# amp01.net
KiCad netlist of a schematic drawn in EAGLE
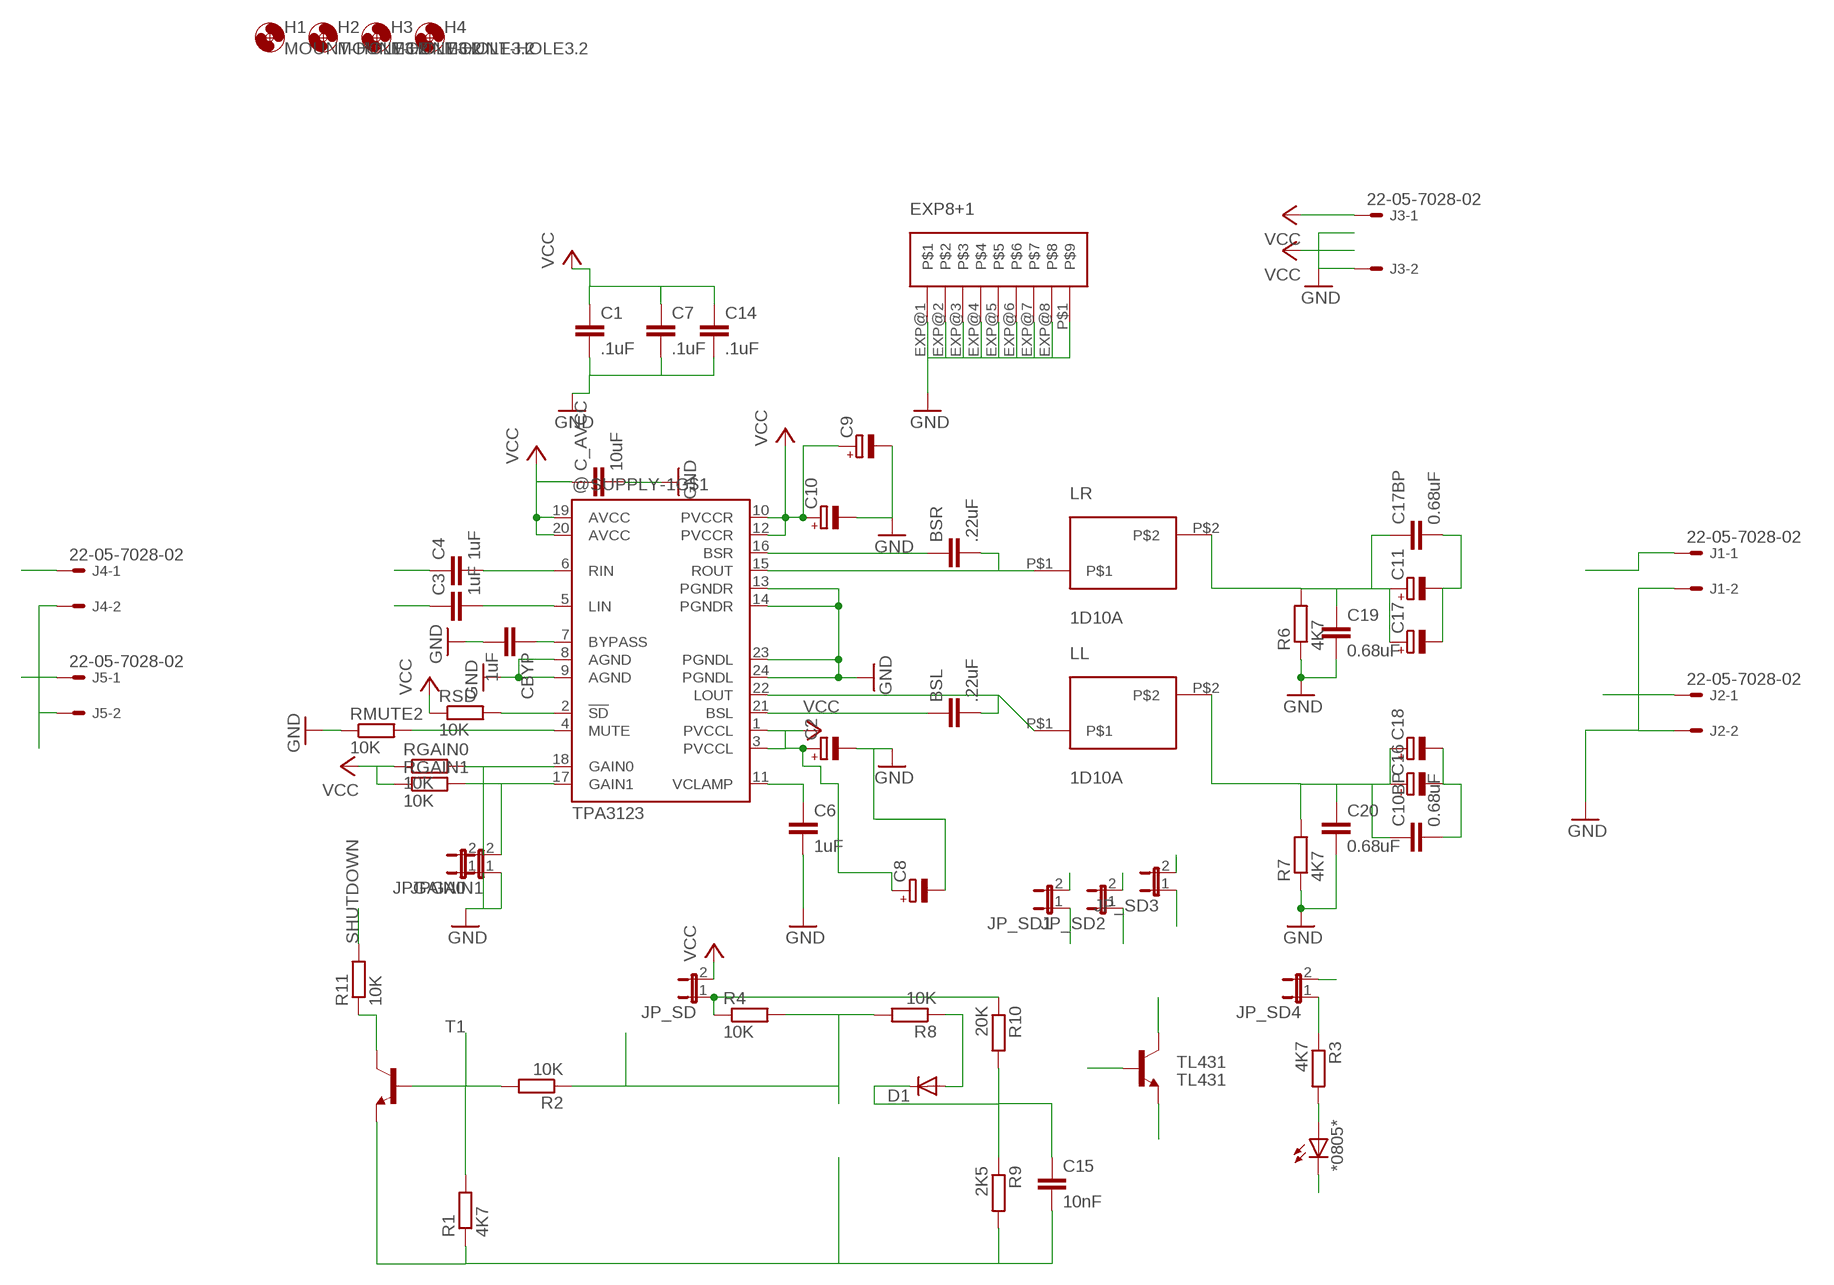
[diagram p0: schematic, sheet 1]

(export (version "E")
  (design (tool "Eeschema 10.0.6"))
  (components
    (comp (ref "*0805*")
      (value "LEDCHIP-LED0805")
      (footprint "eagle-import:CHIP-LED0805")
      (libsource (lib "eagle-import") (part "LEDCHIP-LED0805"))
    )
    (comp (ref "@SUPPLY-1")
      (value "TPA3123")
      (footprint "eagle-import:PWP-TSSOP24")
      (libsource (lib "eagle-import") (part "TPA3123"))
    )
    (comp (ref "BSL")
      (value ".22uF")
      (footprint "eagle-import:C0805")
      (libsource (lib "eagle-import") (part "C-EUC0805"))
    )
    (comp (ref "BSR")
      (value ".22uF")
      (footprint "eagle-import:C0805")
      (libsource (lib "eagle-import") (part "C-EUC0805"))
    )
    (comp (ref "C1")
      (value ".1uF")
      (footprint "eagle-import:C0805")
      (libsource (lib "eagle-import") (part "C-EUC0805"))
    )
    (comp (ref "C2")
      (value "CPOL-EUF")
      (footprint "eagle-import:PANASONIC_F")
      (libsource (lib "eagle-import") (part "CPOL-EUF"))
    )
    (comp (ref "C3")
      (value "1uF")
      (footprint "eagle-import:C050-050X075")
      (libsource (lib "eagle-import") (part "C-EU050-050X075"))
    )
    (comp (ref "C4")
      (value "1uF")
      (footprint "eagle-import:C050-050X075")
      (libsource (lib "eagle-import") (part "C-EU050-050X075"))
    )
    (comp (ref "C6")
      (value "1uF")
      (footprint "eagle-import:C0805")
      (libsource (lib "eagle-import") (part "C-EUC0805"))
    )
    (comp (ref "C7")
      (value ".1uF")
      (footprint "eagle-import:C0805")
      (libsource (lib "eagle-import") (part "C-EUC0805"))
    )
    (comp (ref "C8")
      (value "CPOL-EUF")
      (footprint "eagle-import:PANASONIC_F")
      (libsource (lib "eagle-import") (part "CPOL-EUF"))
    )
    (comp (ref "C9")
      (value "CPOL-EUF")
      (footprint "eagle-import:PANASONIC_F")
      (libsource (lib "eagle-import") (part "CPOL-EUF"))
    )
    (comp (ref "C10")
      (value "CPOL-EUF")
      (footprint "eagle-import:PANASONIC_F")
      (libsource (lib "eagle-import") (part "CPOL-EUF"))
    )
    (comp (ref "C10BP")
      (value "0.68uF")
      (footprint "eagle-import:C050-055X075")
      (libsource (lib "eagle-import") (part "C-EU050-055X075"))
    )
    (comp (ref "C11")
      (value "CPOL-EUF")
      (footprint "eagle-import:PANASONIC_F")
      (libsource (lib "eagle-import") (part "CPOL-EUF"))
    )
    (comp (ref "C14")
      (value ".1uF")
      (footprint "eagle-import:C0805")
      (libsource (lib "eagle-import") (part "C-EUC0805"))
    )
    (comp (ref "C15")
      (value "10nF")
      (footprint "eagle-import:C0805")
      (libsource (lib "eagle-import") (part "C-EUC0805"))
    )
    (comp (ref "C16")
      (value "CPOL-EUF")
      (footprint "eagle-import:PANASONIC_F")
      (libsource (lib "eagle-import") (part "CPOL-EUF"))
    )
    (comp (ref "C17")
      (value "CPOL-EUF")
      (footprint "eagle-import:PANASONIC_F")
      (libsource (lib "eagle-import") (part "CPOL-EUF"))
    )
    (comp (ref "C17BP")
      (value "0.68uF")
      (footprint "eagle-import:C050-055X075")
      (libsource (lib "eagle-import") (part "C-EU050-055X075"))
    )
    (comp (ref "C18")
      (value "CPOL-EUF")
      (footprint "eagle-import:PANASONIC_F")
      (libsource (lib "eagle-import") (part "CPOL-EUF"))
    )
    (comp (ref "C19")
      (value "0.68uF")
      (footprint "eagle-import:C050-055X075")
      (libsource (lib "eagle-import") (part "C-EU050-055X075"))
    )
    (comp (ref "C20")
      (value "0.68uF")
      (footprint "eagle-import:C050-055X075")
      (libsource (lib "eagle-import") (part "C-EU050-055X075"))
    )
    (comp (ref "CBYP")
      (value "1uF")
      (footprint "eagle-import:C0805")
      (libsource (lib "eagle-import") (part "C-EUC0805"))
    )
    (comp (ref "C_AVCC")
      (value "10uF")
      (footprint "eagle-import:C1210")
      (libsource (lib "eagle-import") (part "C-EUC1210"))
    )
    (comp (ref "D1")
      (value "DIODE-MICROMELF-W")
      (footprint "eagle-import:MICROMELF-W")
      (libsource (lib "eagle-import") (part "DIODE-MICROMELF-W"))
    )
    (comp (ref "H1")
      (value "MOUNT-HOLE3.2")
      (footprint "eagle-import:3,2")
      (libsource (lib "eagle-import") (part "MOUNT-HOLE3.2"))
    )
    (comp (ref "H2")
      (value "MOUNT-HOLE3.2")
      (footprint "eagle-import:3,2")
      (libsource (lib "eagle-import") (part "MOUNT-HOLE3.2"))
    )
    (comp (ref "H3")
      (value "MOUNT-HOLE3.2")
      (footprint "eagle-import:3,2")
      (libsource (lib "eagle-import") (part "MOUNT-HOLE3.2"))
    )
    (comp (ref "H4")
      (value "MOUNT-HOLE3.2")
      (footprint "eagle-import:3,2")
      (libsource (lib "eagle-import") (part "MOUNT-HOLE3.2"))
    )
    (comp (ref "J1")
      (value "22-05-7028-02")
      (footprint "eagle-import:7395-02")
      (libsource (lib "eagle-import") (part "22-?-0205-7028"))
    )
    (comp (ref "J2")
      (value "22-05-7028-02")
      (footprint "eagle-import:7395-02")
      (libsource (lib "eagle-import") (part "22-?-0205-7028"))
    )
    (comp (ref "J3")
      (value "22-05-7028-02")
      (footprint "eagle-import:7395-02")
      (fields (field (name "OC_FARNELL") "9731601") (field (name "OC_NEWARK") "unknown"))
      (libsource (lib "eagle-import") (part "22-?-0205-7028"))
    )
    (comp (ref "J4")
      (value "22-05-7028-02")
      (footprint "eagle-import:7395-02")
      (fields (field (name "OC_FARNELL") "9731601") (field (name "OC_NEWARK") "unknown"))
      (libsource (lib "eagle-import") (part "22-?-0205-7028"))
    )
    (comp (ref "J5")
      (value "22-05-7028-02")
      (footprint "eagle-import:7395-02")
      (fields (field (name "OC_FARNELL") "9731601") (field (name "OC_NEWARK") "unknown"))
      (libsource (lib "eagle-import") (part "22-?-0205-7028"))
    )
    (comp (ref "JPGAIN0")
      (value "JUMPER-2SMD-NC")
      (footprint "eagle-import:SJ_2S")
      (libsource (lib "eagle-import") (part "JUMPER-2SMD-NC"))
    )
    (comp (ref "JPGAIN1")
      (value "JUMPER-2SMD-NC")
      (footprint "eagle-import:SJ_2S")
      (libsource (lib "eagle-import") (part "JUMPER-2SMD-NC"))
    )
    (comp (ref "JP_SD")
      (value "JUMPER-2SMD-NC")
      (footprint "eagle-import:SJ_2S")
      (libsource (lib "eagle-import") (part "JUMPER-2SMD-NC"))
    )
    (comp (ref "JP_SD1")
      (value "JUMPER-2SMD-NC")
      (footprint "eagle-import:SJ_2S")
      (libsource (lib "eagle-import") (part "JUMPER-2SMD-NC"))
    )
    (comp (ref "JP_SD2")
      (value "JUMPER-2SMD-NC")
      (footprint "eagle-import:SJ_2S")
      (libsource (lib "eagle-import") (part "JUMPER-2SMD-NC"))
    )
    (comp (ref "JP_SD3")
      (value "JUMPER-2SMD-NC")
      (footprint "eagle-import:SJ_2S")
      (libsource (lib "eagle-import") (part "JUMPER-2SMD-NC"))
    )
    (comp (ref "JP_SD4")
      (value "JUMPER-2SMD-NC")
      (footprint "eagle-import:SJ_2S")
      (libsource (lib "eagle-import") (part "JUMPER-2SMD-NC"))
    )
    (comp (ref "LL")
      (value "1D10A")
      (footprint "eagle-import:1D10APAC")
      (libsource (lib "eagle-import") (part "1D10A"))
    )
    (comp (ref "LR")
      (value "1D10A")
      (footprint "eagle-import:1D10APAC")
      (libsource (lib "eagle-import") (part "1D10A"))
    )
    (comp (ref "R1")
      (value "4K7")
      (footprint "eagle-import:R0805")
      (libsource (lib "eagle-import") (part "R-EU_R0805"))
    )
    (comp (ref "R2")
      (value "10K")
      (footprint "eagle-import:R0805")
      (libsource (lib "eagle-import") (part "R-EU_R0805"))
    )
    (comp (ref "R3")
      (value "4K7")
      (footprint "eagle-import:R0805")
      (libsource (lib "eagle-import") (part "R-EU_R0805"))
    )
    (comp (ref "R4")
      (value "10K")
      (footprint "eagle-import:R0805")
      (libsource (lib "eagle-import") (part "R-EU_R0805"))
    )
    (comp (ref "R6")
      (value "4K7")
      (footprint "eagle-import:R0805")
      (libsource (lib "eagle-import") (part "R-EU_R0805"))
    )
    (comp (ref "R7")
      (value "4K7")
      (footprint "eagle-import:R0805")
      (libsource (lib "eagle-import") (part "R-EU_R0805"))
    )
    (comp (ref "R8")
      (value "10K")
      (footprint "eagle-import:R0805")
      (libsource (lib "eagle-import") (part "R-EU_R0805"))
    )
    (comp (ref "R9")
      (value "2K5")
      (footprint "eagle-import:R0805")
      (libsource (lib "eagle-import") (part "R-EU_R0805"))
    )
    (comp (ref "R10")
      (value "20K")
      (footprint "eagle-import:R0805")
      (libsource (lib "eagle-import") (part "R-EU_R0805"))
    )
    (comp (ref "R11")
      (value "10K")
      (footprint "eagle-import:R0805")
      (libsource (lib "eagle-import") (part "R-EU_R0805"))
    )
    (comp (ref "RGAIN0")
      (value "10K")
      (footprint "eagle-import:R0805")
      (libsource (lib "eagle-import") (part "R-EU_R0805"))
    )
    (comp (ref "RGAIN1")
      (value "10K")
      (footprint "eagle-import:R0805")
      (libsource (lib "eagle-import") (part "R-EU_R0805"))
    )
    (comp (ref "RMUTE2")
      (value "10K")
      (footprint "eagle-import:R0805")
      (libsource (lib "eagle-import") (part "R-EU_R0805"))
    )
    (comp (ref "RSD")
      (value "10K")
      (footprint "eagle-import:R0805")
      (libsource (lib "eagle-import") (part "R-EU_R0805"))
    )
    (comp (ref "T1")
      (value "MMBT3904LT1-NPN-SOT23-BEC")
      (footprint "eagle-import:SOT23-BEC")
      (libsource (lib "eagle-import") (part "-NPN-SOT23-BECMMBT3904LT1"))
    )
    (comp (ref "TL431")
      (value "TL431")
      (footprint "eagle-import:SOT23")
      (libsource (lib "eagle-import") (part "TRANSISTOR_NPNMMBT2222A"))
    )
  )
  (nets
    (net (code "1") (name "/GND2") (class "Default")
      (node (ref "JP_SD2") (pin "2") (pinfunction "2_2") (pintype "passive"))
      (node (ref "JP_SD3") (pin "2") (pinfunction "2_2") (pintype "passive"))
    )
    (net (code "2") (name "/K") (class "Default")
      (node (ref "R2") (pin "1") (pinfunction "1_1") (pintype "passive"))
      (node (ref "R4") (pin "2") (pinfunction "2_2") (pintype "passive"))
      (node (ref "R8") (pin "2") (pinfunction "2_2") (pintype "passive"))
      (node (ref "TL431") (pin "1") (pinfunction "B_1") (pintype "passive"))
    )
    (net (code "3") (name "/LOUT") (class "Default")
      (node (ref "C11") (pin "-") (pinfunction "-_-") (pintype "passive"))
      (node (ref "C17") (pin "-") (pinfunction "-_-") (pintype "passive"))
      (node (ref "C17BP") (pin "2") (pinfunction "2_2") (pintype "passive"))
      (node (ref "J1") (pin "1") (pinfunction "S_1") (pintype "passive"))
    )
    (net (code "4") (name "/N$3") (class "Default")
      (node (ref "C3") (pin "1") (pinfunction "1_1") (pintype "passive"))
      (node (ref "J5") (pin "1") (pinfunction "S_1") (pintype "passive"))
    )
    (net (code "5") (name "/N$9") (class "Default")
      (node (ref "C4") (pin "1") (pinfunction "1_1") (pintype "passive"))
      (node (ref "J4") (pin "1") (pinfunction "S_1") (pintype "passive"))
    )
    (net (code "6") (name "/REF") (class "Default")
      (node (ref "C15") (pin "1") (pinfunction "1_1") (pintype "passive"))
      (node (ref "D1") (pin "C") (pinfunction "C_C") (pintype "passive"))
      (node (ref "R10") (pin "2") (pinfunction "2_2") (pintype "passive"))
      (node (ref "R9") (pin "1") (pinfunction "1_1") (pintype "passive"))
      (node (ref "TL431") (pin "2") (pinfunction "E_2") (pintype "passive"))
    )
    (net (code "7") (name "/ROUT") (class "Default")
      (node (ref "C10BP") (pin "2") (pinfunction "2_2") (pintype "passive"))
      (node (ref "C16") (pin "-") (pinfunction "-_-") (pintype "passive"))
      (node (ref "C18") (pin "-") (pinfunction "-_-") (pintype "passive"))
      (node (ref "J2") (pin "1") (pinfunction "S_1") (pintype "passive"))
    )
    (net (code "8") (name "/SHUTDOWN") (class "Default")
      (node (ref "@SUPPLY-1") (pin "2") (pinfunction "~{SD}_2") (pintype "input"))
      (node (ref "R11") (pin "2") (pinfunction "2_2") (pintype "passive"))
      (node (ref "RSD") (pin "2") (pinfunction "2_2") (pintype "passive"))
    )
    (net (code "9") (name "GND") (class "Default")
      (node (ref "*0805*") (pin "C") (pinfunction "C_C") (pintype "passive"))
      (node (ref "@SUPPLY-1") (pin "13") (pinfunction "PGNDR_13") (pintype "input"))
      (node (ref "@SUPPLY-1") (pin "14") (pinfunction "PGNDR_14") (pintype "input"))
      (node (ref "@SUPPLY-1") (pin "23") (pinfunction "PGNDL_23") (pintype "input"))
      (node (ref "@SUPPLY-1") (pin "24") (pinfunction "PGNDL_24") (pintype "input"))
      (node (ref "@SUPPLY-1") (pin "8") (pinfunction "AGND_8") (pintype "input"))
      (node (ref "@SUPPLY-1") (pin "9") (pinfunction "AGND_9") (pintype "input"))
      (node (ref "@SUPPLY-1") (pin "EXP@1") (pinfunction "P$1_EXP@1") (pintype "bidirectional"))
      (node (ref "@SUPPLY-1") (pin "EXP@2") (pinfunction "P$2_EXP@2") (pintype "bidirectional"))
      (node (ref "@SUPPLY-1") (pin "EXP@3") (pinfunction "P$3_EXP@3") (pintype "bidirectional"))
      (node (ref "@SUPPLY-1") (pin "EXP@4") (pinfunction "P$4_EXP@4") (pintype "bidirectional"))
      (node (ref "@SUPPLY-1") (pin "EXP@5") (pinfunction "P$5_EXP@5") (pintype "bidirectional"))
      (node (ref "@SUPPLY-1") (pin "EXP@6") (pinfunction "P$6_EXP@6") (pintype "bidirectional"))
      (node (ref "@SUPPLY-1") (pin "EXP@7") (pinfunction "P$7_EXP@7") (pintype "bidirectional"))
      (node (ref "@SUPPLY-1") (pin "EXP@8") (pinfunction "P$8_EXP@8") (pintype "bidirectional"))
      (node (ref "@SUPPLY-1") (pin "P$1") (pinfunction "P$9_P$1") (pintype "bidirectional"))
      (node (ref "C1") (pin "2") (pinfunction "2_2") (pintype "passive"))
      (node (ref "C10") (pin "-") (pinfunction "-_-") (pintype "passive"))
      (node (ref "C14") (pin "2") (pinfunction "2_2") (pintype "passive"))
      (node (ref "C15") (pin "2") (pinfunction "2_2") (pintype "passive"))
      (node (ref "C19") (pin "2") (pinfunction "2_2") (pintype "passive"))
      (node (ref "C2") (pin "-") (pinfunction "-_-") (pintype "passive"))
      (node (ref "C20") (pin "2") (pinfunction "2_2") (pintype "passive"))
      (node (ref "C6") (pin "2") (pinfunction "2_2") (pintype "passive"))
      (node (ref "C7") (pin "2") (pinfunction "2_2") (pintype "passive"))
      (node (ref "C8") (pin "-") (pinfunction "-_-") (pintype "passive"))
      (node (ref "C9") (pin "-") (pinfunction "-_-") (pintype "passive"))
      (node (ref "CBYP") (pin "2") (pinfunction "2_2") (pintype "passive"))
      (node (ref "C_AVCC") (pin "2") (pinfunction "2_2") (pintype "passive"))
      (node (ref "J1") (pin "2") (pinfunction "S_2") (pintype "passive"))
      (node (ref "J2") (pin "2") (pinfunction "S_2") (pintype "passive"))
      (node (ref "J3") (pin "2") (pinfunction "S_2") (pintype "passive"))
      (node (ref "J4") (pin "2") (pinfunction "S_2") (pintype "passive"))
      (node (ref "J5") (pin "2") (pinfunction "S_2") (pintype "passive"))
      (node (ref "JPGAIN0") (pin "1") (pinfunction "1_1") (pintype "passive"))
      (node (ref "JPGAIN1") (pin "1") (pinfunction "1_1") (pintype "passive"))
      (node (ref "JP_SD1") (pin "1") (pinfunction "1_1") (pintype "passive"))
      (node (ref "JP_SD2") (pin "1") (pinfunction "1_1") (pintype "passive"))
      (node (ref "JP_SD3") (pin "1") (pinfunction "1_1") (pintype "passive"))
      (node (ref "R1") (pin "1") (pinfunction "1_1") (pintype "passive"))
      (node (ref "R6") (pin "1") (pinfunction "1_1") (pintype "passive"))
      (node (ref "R7") (pin "1") (pinfunction "1_1") (pintype "passive"))
      (node (ref "R9") (pin "2") (pinfunction "2_2") (pintype "passive"))
      (node (ref "RMUTE2") (pin "1") (pinfunction "1_1") (pintype "passive"))
      (node (ref "T1") (pin "E") (pinfunction "E_E") (pintype "passive"))
      (node (ref "TL431") (pin "3") (pinfunction "C_3") (pintype "passive"))
    )
    (net (code "10") (name "Net-(*0805*-PadA)") (class "Default")
      (node (ref "*0805*") (pin "A") (pinfunction "A_A") (pintype "passive"))
      (node (ref "R3") (pin "2") (pinfunction "2_2") (pintype "passive"))
    )
    (net (code "11") (name "Net-(@SUPPLY-1A-BSL)") (class "Default")
      (node (ref "@SUPPLY-1") (pin "21") (pinfunction "BSL_21") (pintype "passive"))
      (node (ref "BSL") (pin "1") (pinfunction "1_1") (pintype "passive"))
    )
    (net (code "12") (name "Net-(@SUPPLY-1A-BSR)") (class "Default")
      (node (ref "@SUPPLY-1") (pin "16") (pinfunction "BSR_16") (pintype "passive"))
      (node (ref "BSR") (pin "1") (pinfunction "1_1") (pintype "passive"))
    )
    (net (code "13") (name "Net-(@SUPPLY-1A-BYPASS)") (class "Default")
      (node (ref "@SUPPLY-1") (pin "7") (pinfunction "BYPASS_7") (pintype "input"))
      (node (ref "CBYP") (pin "1") (pinfunction "1_1") (pintype "passive"))
    )
    (net (code "14") (name "Net-(@SUPPLY-1A-GAIN0)") (class "Default")
      (node (ref "@SUPPLY-1") (pin "18") (pinfunction "GAIN0_18") (pintype "input"))
      (node (ref "JPGAIN0") (pin "2") (pinfunction "2_2") (pintype "passive"))
      (node (ref "RGAIN0") (pin "2") (pinfunction "2_2") (pintype "passive"))
    )
    (net (code "15") (name "Net-(@SUPPLY-1A-GAIN1)") (class "Default")
      (node (ref "@SUPPLY-1") (pin "17") (pinfunction "GAIN1_17") (pintype "input"))
      (node (ref "JPGAIN1") (pin "2") (pinfunction "2_2") (pintype "passive"))
      (node (ref "RGAIN1") (pin "2") (pinfunction "2_2") (pintype "passive"))
    )
    (net (code "16") (name "Net-(@SUPPLY-1A-LIN)") (class "Default")
      (node (ref "@SUPPLY-1") (pin "5") (pinfunction "LIN_5") (pintype "input"))
      (node (ref "C3") (pin "2") (pinfunction "2_2") (pintype "passive"))
    )
    (net (code "17") (name "Net-(@SUPPLY-1A-LOUT)") (class "Default")
      (node (ref "@SUPPLY-1") (pin "22") (pinfunction "LOUT_22") (pintype "output"))
      (node (ref "BSL") (pin "2") (pinfunction "2_2") (pintype "passive"))
      (node (ref "LL") (pin "P$1") (pinfunction "P$1_P$1") (pintype "bidirectional"))
    )
    (net (code "18") (name "Net-(@SUPPLY-1A-MUTE)") (class "Default")
      (node (ref "@SUPPLY-1") (pin "4") (pinfunction "MUTE_4") (pintype "input"))
      (node (ref "RMUTE2") (pin "2") (pinfunction "2_2") (pintype "passive"))
    )
    (net (code "19") (name "Net-(@SUPPLY-1A-RIN)") (class "Default")
      (node (ref "@SUPPLY-1") (pin "6") (pinfunction "RIN_6") (pintype "input"))
      (node (ref "C4") (pin "2") (pinfunction "2_2") (pintype "passive"))
    )
    (net (code "20") (name "Net-(@SUPPLY-1A-ROUT)") (class "Default")
      (node (ref "@SUPPLY-1") (pin "15") (pinfunction "ROUT_15") (pintype "output"))
      (node (ref "BSR") (pin "2") (pinfunction "2_2") (pintype "passive"))
      (node (ref "LR") (pin "P$1") (pinfunction "P$1_P$1") (pintype "bidirectional"))
    )
    (net (code "21") (name "Net-(@SUPPLY-1A-VCLAMP)") (class "Default")
      (node (ref "@SUPPLY-1") (pin "11") (pinfunction "VCLAMP_11") (pintype "input"))
      (node (ref "C6") (pin "1") (pinfunction "1_1") (pintype "passive"))
    )
    (net (code "22") (name "Net-(C10BP-Pad1)") (class "Default")
      (node (ref "C10BP") (pin "1") (pinfunction "1_1") (pintype "passive"))
      (node (ref "C16") (pin "+") (pinfunction "+_+") (pintype "passive"))
      (node (ref "C18") (pin "+") (pinfunction "+_+") (pintype "passive"))
      (node (ref "C20") (pin "1") (pinfunction "1_1") (pintype "passive"))
      (node (ref "LL") (pin "P$2") (pinfunction "P$2_P$2") (pintype "bidirectional"))
      (node (ref "R7") (pin "2") (pinfunction "2_2") (pintype "passive"))
    )
    (net (code "23") (name "Net-(C11-Pad+)") (class "Default")
      (node (ref "C11") (pin "+") (pinfunction "+_+") (pintype "passive"))
      (node (ref "C17") (pin "+") (pinfunction "+_+") (pintype "passive"))
      (node (ref "C17BP") (pin "1") (pinfunction "1_1") (pintype "passive"))
      (node (ref "C19") (pin "1") (pinfunction "1_1") (pintype "passive"))
      (node (ref "LR") (pin "P$2") (pinfunction "P$2_P$2") (pintype "bidirectional"))
      (node (ref "R6") (pin "2") (pinfunction "2_2") (pintype "passive"))
    )
    (net (code "24") (name "Net-(D1-PadA)") (class "Default")
      (node (ref "D1") (pin "A") (pinfunction "A_A") (pintype "passive"))
      (node (ref "R8") (pin "1") (pinfunction "1_1") (pintype "passive"))
    )
    (net (code "25") (name "Net-(JP_SD-Pad1)") (class "Default")
      (node (ref "JP_SD") (pin "1") (pinfunction "1_1") (pintype "passive"))
      (node (ref "R10") (pin "1") (pinfunction "1_1") (pintype "passive"))
      (node (ref "R4") (pin "1") (pinfunction "1_1") (pintype "passive"))
    )
    (net (code "26") (name "Net-(JP_SD4-Pad1)") (class "Default")
      (node (ref "JP_SD4") (pin "1") (pinfunction "1_1") (pintype "passive"))
      (node (ref "R3") (pin "1") (pinfunction "1_1") (pintype "passive"))
    )
    (net (code "27") (name "Net-(R1-Pad2)") (class "Default")
      (node (ref "R1") (pin "2") (pinfunction "2_2") (pintype "passive"))
      (node (ref "R2") (pin "2") (pinfunction "2_2") (pintype "passive"))
      (node (ref "T1") (pin "B") (pinfunction "B_B") (pintype "passive"))
    )
    (net (code "28") (name "Net-(R11-Pad1)") (class "Default")
      (node (ref "R11") (pin "1") (pinfunction "1_1") (pintype "passive"))
      (node (ref "T1") (pin "C") (pinfunction "C_C") (pintype "passive"))
    )
    (net (code "29") (name "VCC") (class "Default")
      (node (ref "@SUPPLY-1") (pin "1") (pinfunction "PVCCL_1") (pintype "input"))
      (node (ref "@SUPPLY-1") (pin "10") (pinfunction "PVCCR_10") (pintype "input"))
      (node (ref "@SUPPLY-1") (pin "12") (pinfunction "PVCCR_12") (pintype "input"))
      (node (ref "@SUPPLY-1") (pin "19") (pinfunction "AVCC_19") (pintype "input"))
      (node (ref "@SUPPLY-1") (pin "20") (pinfunction "AVCC_20") (pintype "input"))
      (node (ref "@SUPPLY-1") (pin "3") (pinfunction "PVCCL_3") (pintype "input"))
      (node (ref "C1") (pin "1") (pinfunction "1_1") (pintype "passive"))
      (node (ref "C10") (pin "+") (pinfunction "+_+") (pintype "passive"))
      (node (ref "C14") (pin "1") (pinfunction "1_1") (pintype "passive"))
      (node (ref "C2") (pin "+") (pinfunction "+_+") (pintype "passive"))
      (node (ref "C7") (pin "1") (pinfunction "1_1") (pintype "passive"))
      (node (ref "C8") (pin "+") (pinfunction "+_+") (pintype "passive"))
      (node (ref "C9") (pin "+") (pinfunction "+_+") (pintype "passive"))
      (node (ref "C_AVCC") (pin "1") (pinfunction "1_1") (pintype "passive"))
      (node (ref "J3") (pin "1") (pinfunction "S_1") (pintype "passive"))
      (node (ref "JP_SD") (pin "2") (pinfunction "2_2") (pintype "passive"))
      (node (ref "JP_SD4") (pin "2") (pinfunction "2_2") (pintype "passive"))
      (node (ref "RGAIN0") (pin "1") (pinfunction "1_1") (pintype "passive"))
      (node (ref "RGAIN1") (pin "1") (pinfunction "1_1") (pintype "passive"))
      (node (ref "RSD") (pin "1") (pinfunction "1_1") (pintype "passive"))
    )
    (net (code "30") (name "unconnected-(JP_SD1-Pad2)") (class "Default")
      (node (ref "JP_SD1") (pin "2") (pinfunction "2_2") (pintype "passive"))
    )
  )
)
